# Loginator.net
KiCad netlist of a schematic drawn in EAGLE
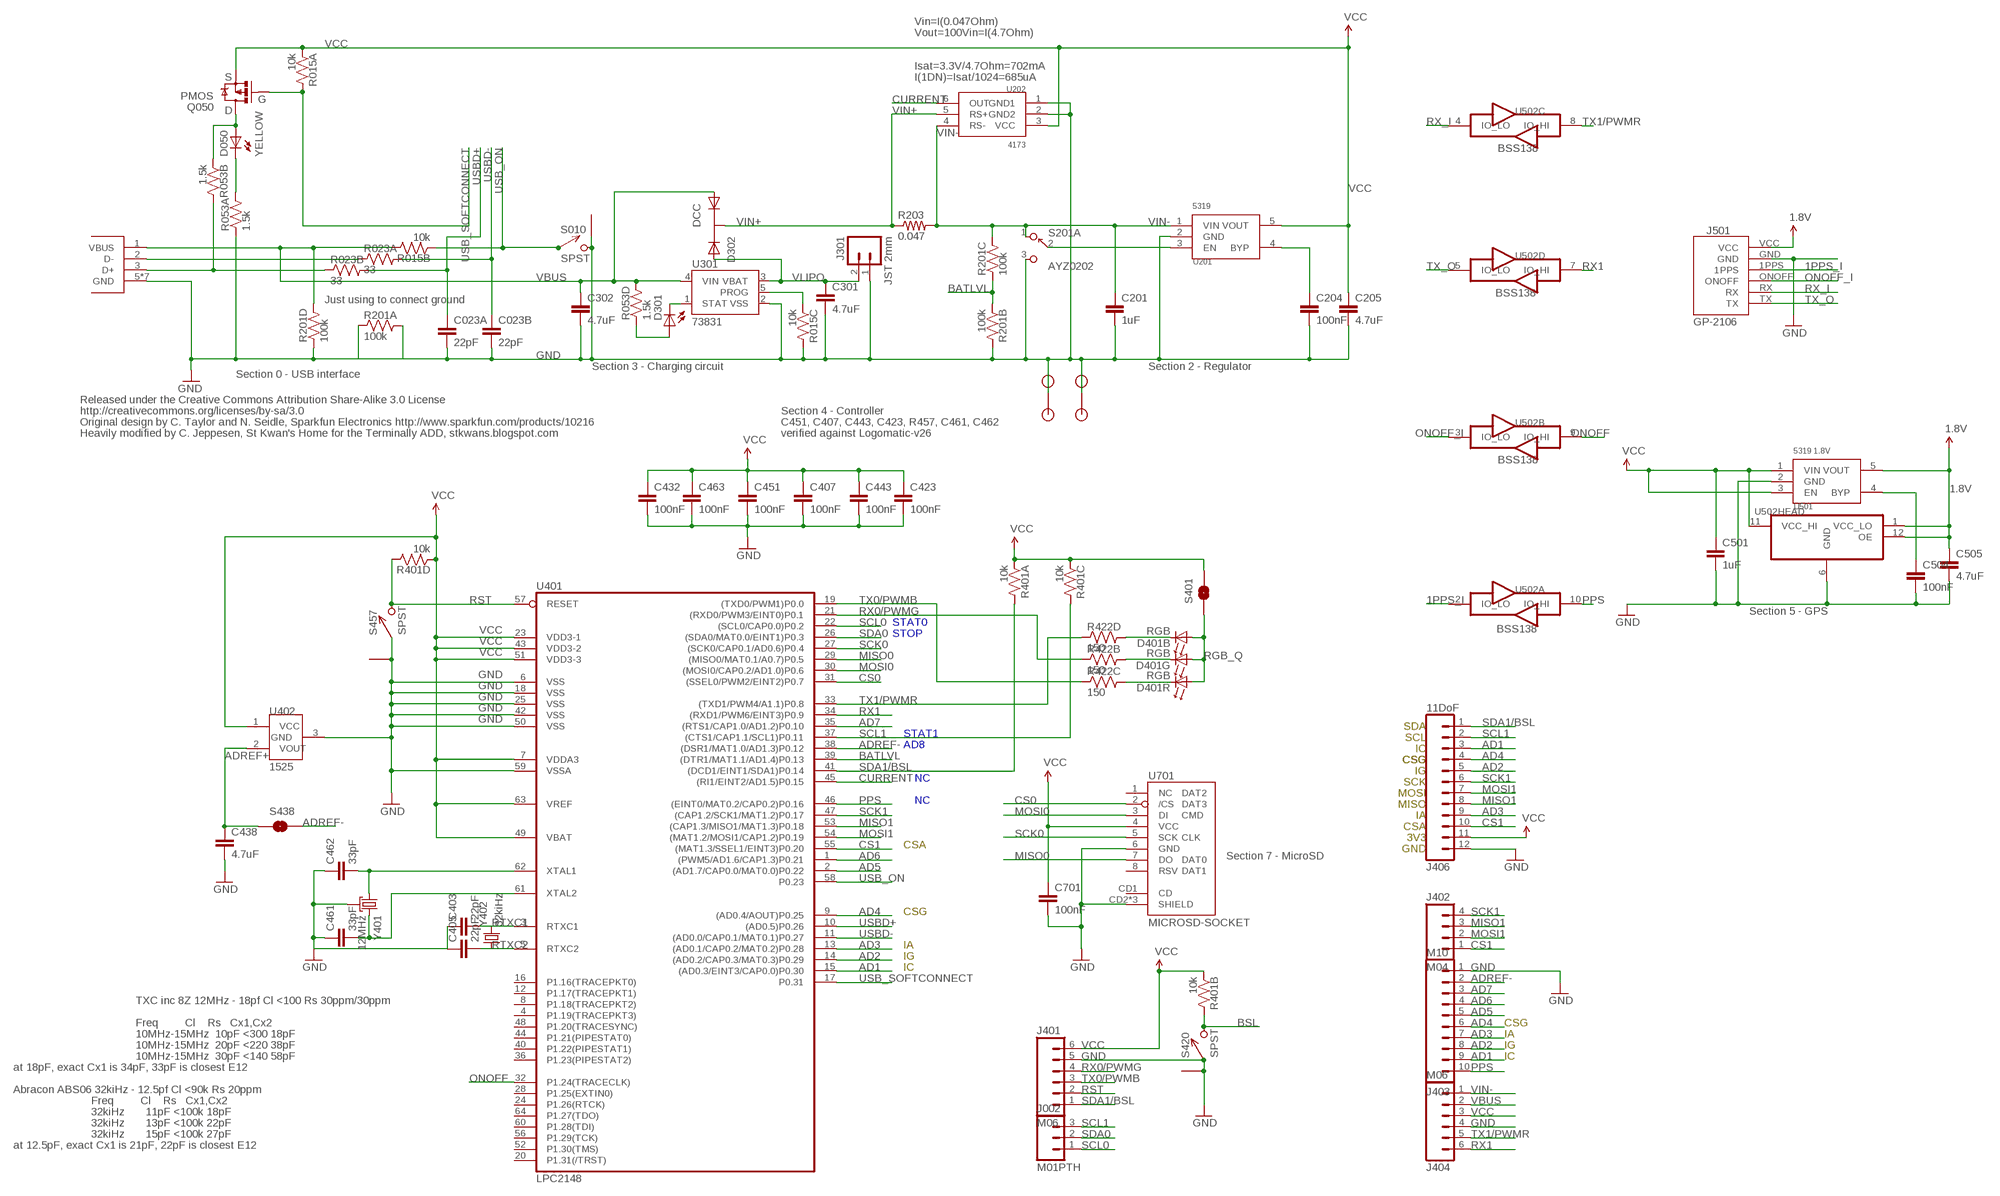
[diagram p0: schematic, sheet 1]

(export (version "E")
  (design (tool "Eeschema 10.0.6"))
  (components
    (comp (ref "C023")
      (value "22pF")
      (footprint "eagle-import:CKCM25")
      (fields (field (name "DIGIKEY") "445-1860-1-ND"))
      (libsource (lib "eagle-import") (part "CKCM25"))
    )
    (comp (ref "C201")
      (value "1uF")
      (footprint "eagle-import:0402-CAP")
      (libsource (lib "eagle-import") (part "CAP0402-CAP"))
    )
    (comp (ref "C204")
      (value "100nF")
      (footprint "eagle-import:0402-CAP")
      (libsource (lib "eagle-import") (part "CAP0402-CAP"))
    )
    (comp (ref "C205")
      (value "4.7uF")
      (footprint "eagle-import:0402-CAP")
      (libsource (lib "eagle-import") (part "CAP0402-CAP"))
    )
    (comp (ref "C301")
      (value "4.7uF")
      (footprint "eagle-import:0402-CAP")
      (libsource (lib "eagle-import") (part "CAP0402-CAP"))
    )
    (comp (ref "C302")
      (value "4.7uF")
      (footprint "eagle-import:0402-CAP")
      (libsource (lib "eagle-import") (part "CAP0402-CAP"))
    )
    (comp (ref "C403")
      (value "22pF")
      (footprint "eagle-import:0402-CAP")
      (libsource (lib "eagle-import") (part "CAP0402-CAP"))
    )
    (comp (ref "C405")
      (value "22pF")
      (footprint "eagle-import:0402-CAP")
      (libsource (lib "eagle-import") (part "CAP0402-CAP"))
    )
    (comp (ref "C407")
      (value "100nF")
      (footprint "eagle-import:0402-CAP")
      (libsource (lib "eagle-import") (part "CAP0402-CAP"))
    )
    (comp (ref "C423")
      (value "100nF")
      (footprint "eagle-import:0402-CAP")
      (libsource (lib "eagle-import") (part "CAP0402-CAP"))
    )
    (comp (ref "C432")
      (value "100nF")
      (footprint "eagle-import:0402-CAP")
      (libsource (lib "eagle-import") (part "CAP0402-CAP"))
    )
    (comp (ref "C438")
      (value "4.7uF")
      (footprint "eagle-import:0402-CAP")
      (libsource (lib "eagle-import") (part "CAP0402-CAP"))
    )
    (comp (ref "C443")
      (value "100nF")
      (footprint "eagle-import:0402-CAP")
      (libsource (lib "eagle-import") (part "CAP0402-CAP"))
    )
    (comp (ref "C451")
      (value "100nF")
      (footprint "eagle-import:0402-CAP")
      (libsource (lib "eagle-import") (part "CAP0402-CAP"))
    )
    (comp (ref "C461")
      (value "33pF")
      (footprint "eagle-import:0402-CAP")
      (libsource (lib "eagle-import") (part "CAP0402-CAP"))
    )
    (comp (ref "C462")
      (value "33pF")
      (footprint "eagle-import:0402-CAP")
      (libsource (lib "eagle-import") (part "CAP0402-CAP"))
    )
    (comp (ref "C463")
      (value "100nF")
      (footprint "eagle-import:0402-CAP")
      (libsource (lib "eagle-import") (part "CAP0402-CAP"))
    )
    (comp (ref "C501")
      (value "1uF")
      (footprint "eagle-import:0402-CAP")
      (libsource (lib "eagle-import") (part "CAP0402-CAP"))
    )
    (comp (ref "C504")
      (value "100nF")
      (footprint "eagle-import:0402-CAP")
      (libsource (lib "eagle-import") (part "CAP0402-CAP"))
    )
    (comp (ref "C505")
      (value "4.7uF")
      (footprint "eagle-import:0402-CAP")
      (libsource (lib "eagle-import") (part "CAP0402-CAP"))
    )
    (comp (ref "C701")
      (value "100nF")
      (footprint "eagle-import:0402-CAP")
      (libsource (lib "eagle-import") (part "CAP0402-CAP"))
    )
    (comp (ref "D050")
      (value "YELLOW")
      (footprint "eagle-import:LED-0603")
      (libsource (lib "eagle-import") (part "LED0603"))
    )
    (comp (ref "D301")
      (value "BLUE")
      (footprint "eagle-import:LED-0603")
      (libsource (lib "eagle-import") (part "LED0603"))
    )
    (comp (ref "D302")
      (value "DCC")
      (footprint "eagle-import:SOT-23-3")
      (libsource (lib "eagle-import") (part "PMEG2005CT"))
    )
    (comp (ref "D401")
      (value "RGB")
      (footprint "eagle-import:SMLP36")
      (fields (field (name "DIGIKEY") "846-1097-1-ND"))
      (libsource (lib "eagle-import") (part "SMLP36RGB2W(R)"))
    )
    (comp (ref "J001")
      (value "USB_MICROB_JSTGCT")
      (footprint "eagle-import:USB_MICROB_3075")
      (libsource (lib "eagle-import") (part "USB_MICROB_JSTGCT"))
    )
    (comp (ref "J002")
      (value "M01PTH")
      (footprint "eagle-import:1X03")
      (libsource (lib "eagle-import") (part "M03PTH"))
    )
    (comp (ref "J301")
      (value "JST 2mm")
      (footprint "eagle-import:JST-2-SMD")
      (libsource (lib "eagle-import") (part "M02-JST-2MM-SMT"))
    )
    (comp (ref "J401")
      (value "M06")
      (footprint "eagle-import:1X06")
      (libsource (lib "eagle-import") (part "M06SIP"))
    )
    (comp (ref "J402")
      (value "M04")
      (footprint "eagle-import:1X04")
      (libsource (lib "eagle-import") (part "M04PTH"))
    )
    (comp (ref "J403")
      (value "M10")
      (footprint "eagle-import:1X10")
      (libsource (lib "eagle-import") (part "M10{dblquote}"))
    )
    (comp (ref "J404")
      (value "M06")
      (footprint "eagle-import:1X06")
      (libsource (lib "eagle-import") (part "M06SIP"))
    )
    (comp (ref "J406")
      (value "11DoF")
      (footprint "eagle-import:1X12")
      (libsource (lib "eagle-import") (part "M12PTH"))
    )
    (comp (ref "J501")
      (value "GP-2106")
      (footprint "eagle-import:GP-2106")
      (libsource (lib "eagle-import") (part "GP-2106"))
    )
    (comp (ref "JP1")
      (value "STANDOFF")
      (footprint "eagle-import:STANDOFF")
      (libsource (lib "eagle-import") (part "STANDOFF"))
    )
    (comp (ref "JP2")
      (value "STANDOFF")
      (footprint "eagle-import:STANDOFF")
      (libsource (lib "eagle-import") (part "STANDOFF"))
    )
    (comp (ref "JP3")
      (value "STANDOFF")
      (footprint "eagle-import:STANDOFF")
      (libsource (lib "eagle-import") (part "STANDOFF"))
    )
    (comp (ref "JP4")
      (value "STANDOFF")
      (footprint "eagle-import:STANDOFF")
      (libsource (lib "eagle-import") (part "STANDOFF"))
    )
    (comp (ref "Q050")
      (value "PMOS")
      (footprint "eagle-import:SOT23-3")
      (libsource (lib "eagle-import") (part "MOSFET-PCHANNELSMD"))
    )
    (comp (ref "R015")
      (value "10k")
      (footprint "eagle-import:CRA04")
      (fields (field (name "DIGIKEY") "CRA4S810KCT-ND"))
      (libsource (lib "eagle-import") (part "RP404"))
    )
    (comp (ref "R023")
      (value "33")
      (footprint "eagle-import:CRA02")
      (fields (field (name "DIGIKEY") "Y5330CT-ND"))
      (libsource (lib "eagle-import") (part "RP2EXB24V"))
    )
    (comp (ref "R053")
      (value "1.5k")
      (footprint "eagle-import:CRA04")
      (fields (field (name "DIGIKEY") "CRA4S81.5KCT-ND"))
      (libsource (lib "eagle-import") (part "RP404"))
    )
    (comp (ref "R201")
      (value "100k")
      (footprint "eagle-import:CRA04")
      (fields (field (name "DIGIKEY") "CRA4S8100KCT-ND"))
      (libsource (lib "eagle-import") (part "RP404"))
    )
    (comp (ref "R203")
      (value "0.047")
      (footprint "eagle-import:0402-RES")
      (libsource (lib "eagle-import") (part "RESISTOR0402-RES"))
    )
    (comp (ref "R401")
      (value "10k")
      (footprint "eagle-import:CRA04")
      (fields (field (name "DIGIKEY") "CRA4S810KCT-ND"))
      (libsource (lib "eagle-import") (part "RP404"))
    )
    (comp (ref "R422")
      (value "150")
      (footprint "eagle-import:CRA04")
      (fields (field (name "DIGIKEY") "CRA4P8150CT-ND"))
      (libsource (lib "eagle-import") (part "RP404"))
    )
    (comp (ref "S010")
      (value "SPST")
      (footprint "eagle-import:B3U-1100P")
      (fields (field (name "DIGIKEY") "SW1021CT-ND"))
      (libsource (lib "eagle-import") (part "B3U-1100P"))
    )
    (comp (ref "S201")
      (value "AYZ0202")
      (footprint "eagle-import:AYZ0202")
      (libsource (lib "eagle-import") (part "AYZ0202"))
    )
    (comp (ref "S401")
      (value "SOLDERJUMPERNO")
      (footprint "eagle-import:SJ_2S-NO")
      (libsource (lib "eagle-import") (part "SOLDERJUMPERNO"))
    )
    (comp (ref "S420")
      (value "SPST")
      (footprint "eagle-import:B3U-1100P")
      (fields (field (name "DIGIKEY") "SW1021CT-ND"))
      (libsource (lib "eagle-import") (part "B3U-1100P"))
    )
    (comp (ref "S438")
      (value "SOLDERJUMPERNO")
      (footprint "eagle-import:SJ_2S-NO")
      (libsource (lib "eagle-import") (part "SOLDERJUMPERNO"))
    )
    (comp (ref "S457")
      (value "SPST")
      (footprint "eagle-import:B3U-1100P")
      (fields (field (name "DIGIKEY") "SW1021CT-ND"))
      (libsource (lib "eagle-import") (part "B3U-1100P"))
    )
    (comp (ref "U201")
      (value "5319")
      (footprint "eagle-import:SOT-23-5")
      (libsource (lib "eagle-import") (part "MIC5319D5"))
    )
    (comp (ref "U202")
      (value "4173")
      (footprint "eagle-import:SOT-23-6")
      (libsource (lib "eagle-import") (part "MAX4173"))
    )
    (comp (ref "U301")
      (value "73831")
      (footprint "eagle-import:SOT23-5")
      (libsource (lib "eagle-import") (part "MCP73831"))
    )
    (comp (ref "U401")
      (value "LPC2148")
      (footprint "eagle-import:SQFP-S-10X10-64")
      (libsource (lib "eagle-import") (part "LPC213X"))
    )
    (comp (ref "U402")
      (value "1525")
      (footprint "eagle-import:SOT-23-3")
      (libsource (lib "eagle-import") (part "MCP1525"))
    )
    (comp (ref "U501")
      (value "5319 1.8V")
      (footprint "eagle-import:SOT-23-5")
      (libsource (lib "eagle-import") (part "MIC5319D5"))
    )
    (comp (ref "U502")
      (value "TXB0104RUT")
      (footprint "eagle-import:R-PUQFN-N12")
      (fields (field (name "DIGIKEY") "296-25888-1-ND"))
      (libsource (lib "eagle-import") (part "TXB0104RUT"))
    )
    (comp (ref "U701")
      (value "MICROSD-SOCKET")
      (footprint "eagle-import:MICROSD-SOCKET-PP")
      (libsource (lib "eagle-import") (part "MICROSD-SOCKET"))
    )
    (comp (ref "Y401")
      (value "12MHz")
      (footprint "eagle-import:CRYSTAL_SMD_2MM_2_5MM")
      (libsource (lib "eagle-import") (part "CX2520"))
    )
    (comp (ref "Y402")
      (value "32kiHz")
      (footprint "eagle-import:ABS06")
      (libsource (lib "eagle-import") (part "ABS06"))
    )
  )
  (nets
    (net (code "1") (name "/1PPS_I") (class "Default")
      (node (ref "J501") (pin "1PPS") (pinfunction "1PPS_1PPS") (pintype "bidirectional"))
      (node (ref "U502") (pin "2") (pinfunction "IO_LO_2") (pintype "bidirectional"))
    )
    (net (code "2") (name "/AD1") (class "Default")
      (node (ref "J403") (pin "9") (pinfunction "9_9") (pintype "passive"))
      (node (ref "J406") (pin "3") (pinfunction "3_3") (pintype "passive"))
      (node (ref "U401") (pin "15") (pinfunction "(AD0.3/EINT3/CAP0.0)P0.30_15") (pintype "bidirectional"))
    )
    (net (code "3") (name "/AD2") (class "Default")
      (node (ref "J403") (pin "8") (pinfunction "8_8") (pintype "passive"))
      (node (ref "J406") (pin "5") (pinfunction "5_5") (pintype "passive"))
      (node (ref "U401") (pin "14") (pinfunction "(AD0.2/CAP0.3/MAT0.3)P0.29_14") (pintype "bidirectional"))
    )
    (net (code "4") (name "/AD3") (class "Default")
      (node (ref "J403") (pin "7") (pinfunction "7_7") (pintype "passive"))
      (node (ref "J406") (pin "9") (pinfunction "9_9") (pintype "passive"))
      (node (ref "U401") (pin "13") (pinfunction "(AD0.1/CAP0.2/MAT0.2)P0.28_13") (pintype "bidirectional"))
    )
    (net (code "5") (name "/AD4") (class "Default")
      (node (ref "J403") (pin "6") (pinfunction "6_6") (pintype "passive"))
      (node (ref "J406") (pin "4") (pinfunction "4_4") (pintype "passive"))
      (node (ref "U401") (pin "9") (pinfunction "(AD0.4/AOUT)P0.25_9") (pintype "bidirectional"))
    )
    (net (code "6") (name "/AD5") (class "Default")
      (node (ref "J403") (pin "5") (pinfunction "5_5") (pintype "passive"))
      (node (ref "U401") (pin "2") (pinfunction "(AD1.7/CAP0.0/MAT0.0)P0.22_2") (pintype "bidirectional"))
    )
    (net (code "7") (name "/AD6") (class "Default")
      (node (ref "J403") (pin "4") (pinfunction "4_4") (pintype "passive"))
      (node (ref "U401") (pin "1") (pinfunction "(PWM5/AD1.6/CAP1.3)P0.21_1") (pintype "bidirectional"))
    )
    (net (code "8") (name "/AD7") (class "Default")
      (node (ref "J403") (pin "3") (pinfunction "3_3") (pintype "passive"))
      (node (ref "U401") (pin "35") (pinfunction "(RTS1/CAP1.0/AD1.2)P0.10_35") (pintype "bidirectional"))
    )
    (net (code "9") (name "/ADREF+") (class "Default")
      (node (ref "C438") (pin "1") (pinfunction "1_1") (pintype "passive"))
      (node (ref "S438") (pin "1") (pinfunction "1_1") (pintype "passive"))
      (node (ref "U402") (pin "2") (pinfunction "VOUT_2") (pintype "bidirectional"))
    )
    (net (code "10") (name "/ADREF-") (class "Default")
      (node (ref "J403") (pin "2") (pinfunction "2_2") (pintype "passive"))
      (node (ref "S438") (pin "2") (pinfunction "2_2") (pintype "passive"))
      (node (ref "U401") (pin "38") (pinfunction "(DSR1/MAT1.0/AD1.3)P0.12_38") (pintype "bidirectional"))
    )
    (net (code "11") (name "/BATLVL") (class "Default")
      (node (ref "R201") (pin "2") (pinfunction "1_2") (pintype "passive"))
      (node (ref "R201") (pin "3") (pinfunction "1_3") (pintype "passive"))
      (node (ref "U401") (pin "39") (pinfunction "(DTR1/MAT1.1/AD1.4)P0.13_39") (pintype "bidirectional"))
    )
    (net (code "12") (name "/BSL") (class "Default")
      (node (ref "R401") (pin "7") (pinfunction "2_7") (pintype "passive"))
      (node (ref "S420") (pin "P$2") (pinfunction "2_P$2") (pintype "bidirectional"))
    )
    (net (code "13") (name "/CS0") (class "Default")
      (node (ref "U401") (pin "31") (pinfunction "(SSEL0/PWM2/EINT2)P0.7_31") (pintype "bidirectional"))
      (node (ref "U701") (pin "2") (pinfunction "/CS_2") (pintype "bidirectional"))
    )
    (net (code "14") (name "/CS1") (class "Default")
      (node (ref "J402") (pin "1") (pinfunction "1_1") (pintype "passive"))
      (node (ref "J406") (pin "10") (pinfunction "10_10") (pintype "passive"))
      (node (ref "U401") (pin "55") (pinfunction "(MAT1.3/SSEL1/EINT3)P0.20_55") (pintype "bidirectional"))
    )
    (net (code "15") (name "/CURRENT") (class "Default")
      (node (ref "U202") (pin "6") (pinfunction "OUT_6") (pintype "bidirectional"))
      (node (ref "U401") (pin "45") (pinfunction "(RI1/EINT2/AD1.5)P0.15_45") (pintype "bidirectional"))
    )
    (net (code "16") (name "/MISO0") (class "Default")
      (node (ref "U401") (pin "29") (pinfunction "(MISO0/MAT0.1/A0.7)P0.5_29") (pintype "bidirectional"))
      (node (ref "U701") (pin "7") (pinfunction "DO_7") (pintype "bidirectional"))
    )
    (net (code "17") (name "/MISO1") (class "Default")
      (node (ref "J402") (pin "3") (pinfunction "3_3") (pintype "passive"))
      (node (ref "J406") (pin "8") (pinfunction "8_8") (pintype "passive"))
      (node (ref "U401") (pin "53") (pinfunction "(CAP1.3/MISO1/MAT1.3)P0.18_53") (pintype "bidirectional"))
    )
    (net (code "18") (name "/MOSI0") (class "Default")
      (node (ref "U401") (pin "30") (pinfunction "(MOSI0/CAP0.2/AD1.0)P0.6_30") (pintype "bidirectional"))
      (node (ref "U701") (pin "3") (pinfunction "DI_3") (pintype "bidirectional"))
    )
    (net (code "19") (name "/MOSI1") (class "Default")
      (node (ref "J402") (pin "2") (pinfunction "2_2") (pintype "passive"))
      (node (ref "J406") (pin "7") (pinfunction "7_7") (pintype "passive"))
      (node (ref "U401") (pin "54") (pinfunction "(MAT1.2/MOSI1/CAP1.2)P0.19_54") (pintype "bidirectional"))
    )
    (net (code "20") (name "/ONOFF") (class "Default")
      (node (ref "U401") (pin "32") (pinfunction "P1.24(TRACECLK)_32") (pintype "bidirectional"))
      (node (ref "U502") (pin "9") (pinfunction "IO_HI_9") (pintype "bidirectional"))
    )
    (net (code "21") (name "/ONOFF_I") (class "Default")
      (node (ref "J501") (pin "ONOFF") (pinfunction "ONOFF_ONOFF") (pintype "bidirectional"))
      (node (ref "U502") (pin "3") (pinfunction "IO_LO_3") (pintype "bidirectional"))
    )
    (net (code "22") (name "/PPS") (class "Default")
      (node (ref "J403") (pin "10") (pinfunction "10_10") (pintype "passive"))
      (node (ref "U401") (pin "46") (pinfunction "(EINT0/MAT0.2/CAP0.2)P0.16_46") (pintype "bidirectional"))
      (node (ref "U502") (pin "10") (pinfunction "IO_HI_10") (pintype "bidirectional"))
    )
    (net (code "23") (name "/RGB_Q") (class "Default")
      (node (ref "D401") (pin "2") (pinfunction "A_2") (pintype "passive"))
      (node (ref "D401") (pin "4") (pinfunction "A_4") (pintype "passive"))
      (node (ref "D401") (pin "6") (pinfunction "A_6") (pintype "passive"))
      (node (ref "S401") (pin "1") (pinfunction "1_1") (pintype "passive"))
    )
    (net (code "24") (name "/RST") (class "Default")
      (node (ref "J401") (pin "2") (pinfunction "2_2") (pintype "passive"))
      (node (ref "R401") (pin "5") (pinfunction "2_5") (pintype "passive"))
      (node (ref "S457") (pin "P$2") (pinfunction "2_P$2") (pintype "bidirectional"))
      (node (ref "U401") (pin "57") (pinfunction "RESET_57") (pintype "input"))
    )
    (net (code "25") (name "/RTXC1") (class "Default")
      (node (ref "C403") (pin "2") (pinfunction "2_2") (pintype "passive"))
      (node (ref "U401") (pin "3") (pinfunction "RTXC1_3") (pintype "input"))
      (node (ref "Y402") (pin "2") (pinfunction "2_2") (pintype "passive"))
    )
    (net (code "26") (name "/RTXC2") (class "Default")
      (node (ref "C405") (pin "2") (pinfunction "2_2") (pintype "passive"))
      (node (ref "U401") (pin "5") (pinfunction "RTXC2_5") (pintype "output"))
      (node (ref "Y402") (pin "1") (pinfunction "1_1") (pintype "passive"))
    )
    (net (code "27") (name "/RX0{slash}PWMG") (class "Default")
      (node (ref "J401") (pin "4") (pinfunction "4_4") (pintype "passive"))
      (node (ref "R422") (pin "2") (pinfunction "1_2") (pintype "passive"))
      (node (ref "U401") (pin "21") (pinfunction "(RXD0/PWM3/EINT0)P0.1_21") (pintype "bidirectional"))
    )
    (net (code "28") (name "/RX1") (class "Default")
      (node (ref "J404") (pin "6") (pinfunction "6_6") (pintype "passive"))
      (node (ref "U401") (pin "34") (pinfunction "(RXD1/PWM6/EINT3)P0.9_34") (pintype "bidirectional"))
      (node (ref "U502") (pin "7") (pinfunction "IO_HI_7") (pintype "bidirectional"))
    )
    (net (code "29") (name "/RX_I") (class "Default")
      (node (ref "J501") (pin "RX") (pinfunction "RX_RX") (pintype "bidirectional"))
      (node (ref "U502") (pin "4") (pinfunction "IO_LO_4") (pintype "bidirectional"))
    )
    (net (code "30") (name "/SCK0") (class "Default")
      (node (ref "U401") (pin "27") (pinfunction "(SCK0/CAP0.1/AD0.6)P0.4_27") (pintype "bidirectional"))
      (node (ref "U701") (pin "5") (pinfunction "SCK_5") (pintype "bidirectional"))
    )
    (net (code "31") (name "/SCK1") (class "Default")
      (node (ref "J402") (pin "4") (pinfunction "4_4") (pintype "passive"))
      (node (ref "J406") (pin "6") (pinfunction "6_6") (pintype "passive"))
      (node (ref "U401") (pin "47") (pinfunction "(CAP1.2/SCK1/MAT1.2)P0.17_47") (pintype "bidirectional"))
    )
    (net (code "32") (name "/SCL0") (class "Default")
      (node (ref "J002") (pin "1") (pinfunction "1_1") (pintype "passive"))
      (node (ref "U401") (pin "22") (pinfunction "(SCL0/CAP0.0)P0.2_22") (pintype "bidirectional"))
    )
    (net (code "33") (name "/SCL1") (class "Default")
      (node (ref "J002") (pin "3") (pinfunction "3_3") (pintype "passive"))
      (node (ref "J406") (pin "2") (pinfunction "2_2") (pintype "passive"))
      (node (ref "R401") (pin "6") (pinfunction "2_6") (pintype "passive"))
      (node (ref "U401") (pin "37") (pinfunction "(CTS1/CAP1.1/SCL1)P0.11_37") (pintype "bidirectional"))
    )
    (net (code "34") (name "/SDA0") (class "Default")
      (node (ref "J002") (pin "2") (pinfunction "2_2") (pintype "passive"))
      (node (ref "U401") (pin "26") (pinfunction "(SDA0/MAT0.0/EINT1)P0.3_26") (pintype "bidirectional"))
    )
    (net (code "35") (name "/SDA1{slash}BSL") (class "Default")
      (node (ref "J401") (pin "1") (pinfunction "1_1") (pintype "passive"))
      (node (ref "J406") (pin "1") (pinfunction "1_1") (pintype "passive"))
      (node (ref "R401") (pin "8") (pinfunction "2_8") (pintype "passive"))
      (node (ref "U401") (pin "41") (pinfunction "(DCD1/EINT1/SDA1)P0.14_41") (pintype "bidirectional"))
    )
    (net (code "36") (name "/TX0{slash}PWMB") (class "Default")
      (node (ref "J401") (pin "3") (pinfunction "3_3") (pintype "passive"))
      (node (ref "R422") (pin "3") (pinfunction "1_3") (pintype "passive"))
      (node (ref "U401") (pin "19") (pinfunction "(TXD0/PWM1)P0.0_19") (pintype "bidirectional"))
    )
    (net (code "37") (name "/TX1{slash}PWMR") (class "Default")
      (node (ref "J404") (pin "5") (pinfunction "5_5") (pintype "passive"))
      (node (ref "R422") (pin "4") (pinfunction "1_4") (pintype "passive"))
      (node (ref "U401") (pin "33") (pinfunction "(TXD1/PWM4/A1.1)P0.8_33") (pintype "bidirectional"))
      (node (ref "U502") (pin "8") (pinfunction "IO_HI_8") (pintype "bidirectional"))
    )
    (net (code "38") (name "/TX_O") (class "Default")
      (node (ref "J501") (pin "TX") (pinfunction "TX_TX") (pintype "bidirectional"))
      (node (ref "U502") (pin "5") (pinfunction "IO_LO_5") (pintype "bidirectional"))
    )
    (net (code "39") (name "/USBD+") (class "Default")
      (node (ref "C023") (pin "1") (pinfunction "1_1") (pintype "passive"))
      (node (ref "R023") (pin "3") (pinfunction "2_3") (pintype "passive"))
      (node (ref "U401") (pin "10") (pinfunction "(AD0.5)P0.26_10") (pintype "bidirectional"))
    )
    (net (code "40") (name "/USBD-") (class "Default")
      (node (ref "C023") (pin "2") (pinfunction "1_2") (pintype "passive"))
      (node (ref "R023") (pin "4") (pinfunction "2_4") (pintype "passive"))
      (node (ref "U401") (pin "11") (pinfunction "(AD0.0/CAP0.1/MAT0.1)P0.27_11") (pintype "bidirectional"))
    )
    (net (code "41") (name "/USB_ON") (class "Default")
      (node (ref "R015") (pin "2") (pinfunction "1_2") (pintype "passive"))
      (node (ref "S010") (pin "P$1") (pinfunction "1_P$1") (pintype "bidirectional"))
      (node (ref "U401") (pin "58") (pinfunction "P0.23_58") (pintype "bidirectional"))
    )
    (net (code "42") (name "/USB_SOFTCONNECT") (class "Default")
      (node (ref "Q050") (pin "1") (pinfunction "G_1") (pintype "passive"))
      (node (ref "R015") (pin "8") (pinfunction "2_8") (pintype "passive"))
      (node (ref "U401") (pin "17") (pinfunction "P0.31_17") (pintype "output"))
    )
    (net (code "43") (name "/VBUS") (class "Default")
      (node (ref "C302") (pin "1") (pinfunction "1_1") (pintype "passive"))
      (node (ref "D302") (pin "1") (pinfunction "A1_1") (pintype "passive"))
      (node (ref "J001") (pin "1") (pinfunction "VBUS_1") (pintype "bidirectional"))
      (node (ref "J404") (pin "2") (pinfunction "2_2") (pintype "passive"))
      (node (ref "R015") (pin "7") (pinfunction "2_7") (pintype "passive"))
      (node (ref "R053") (pin "5") (pinfunction "2_5") (pintype "passive"))
      (node (ref "R201") (pin "5") (pinfunction "2_5") (pintype "passive"))
      (node (ref "U301") (pin "4") (pinfunction "VIN_4") (pintype "power_in"))
    )
    (net (code "44") (name "/VIN+") (class "Default")
      (node (ref "D302") (pin "3") (pinfunction "K_3") (pintype "passive"))
      (node (ref "R203") (pin "1") (pinfunction "1_1") (pintype "passive"))
      (node (ref "U202") (pin "5") (pinfunction "RS+_5") (pintype "bidirectional"))
    )
    (net (code "45") (name "/VIN-") (class "Default")
      (node (ref "C201") (pin "1") (pinfunction "1_1") (pintype "passive"))
      (node (ref "J404") (pin "1") (pinfunction "1_1") (pintype "passive"))
      (node (ref "R201") (pin "6") (pinfunction "2_6") (pintype "passive"))
      (node (ref "R203") (pin "2") (pinfunction "2_2") (pintype "passive"))
      (node (ref "S201") (pin "1") (pinfunction "P$1_1") (pintype "bidirectional"))
      (node (ref "U201") (pin "1") (pinfunction "VIN_1") (pintype "bidirectional"))
      (node (ref "U202") (pin "4") (pinfunction "RS-_4") (pintype "bidirectional"))
    )
    (net (code "46") (name "/VLIPO") (class "Default")
      (node (ref "C301") (pin "1") (pinfunction "1_1") (pintype "passive"))
      (node (ref "D302") (pin "2") (pinfunction "A2_2") (pintype "passive"))
      (node (ref "J301") (pin "2") (pinfunction "2_2") (pintype "passive"))
      (node (ref "U301") (pin "3") (pinfunction "VBAT_3") (pintype "power_in"))
    )
    (net (code "47") (name "1.8V") (class "Default")
      (node (ref "C505") (pin "1") (pinfunction "1_1") (pintype "passive"))
      (node (ref "J501") (pin "VCC") (pinfunction "VCC_VCC") (pintype "bidirectional"))
      (node (ref "U501") (pin "5") (pinfunction "VOUT_5") (pintype "bidirectional"))
      (node (ref "U502") (pin "1") (pinfunction "VCC_LO_1") (pintype "power_in"))
      (node (ref "U502") (pin "12") (pinfunction "OE_12") (pintype "bidirectional"))
    )
    (net (code "48") (name "GND") (class "Default")
      (node (ref "C023") (pin "3") (pinfunction "2_3") (pintype "passive"))
      (node (ref "C023") (pin "4") (pinfunction "2_4") (pintype "passive"))
      (node (ref "C201") (pin "2") (pinfunction "2_2") (pintype "passive"))
      (node (ref "C204") (pin "2") (pinfunction "2_2") (pintype "passive"))
      (node (ref "C205") (pin "2") (pinfunction "2_2") (pintype "passive"))
      (node (ref "C301") (pin "2") (pinfunction "2_2") (pintype "passive"))
      (node (ref "C302") (pin "2") (pinfunction "2_2") (pintype "passive"))
      (node (ref "C403") (pin "1") (pinfunction "1_1") (pintype "passive"))
      (node (ref "C405") (pin "1") (pinfunction "1_1") (pintype "passive"))
      (node (ref "C407") (pin "2") (pinfunction "2_2") (pintype "passive"))
      (node (ref "C423") (pin "2") (pinfunction "2_2") (pintype "passive"))
      (node (ref "C432") (pin "2") (pinfunction "2_2") (pintype "passive"))
      (node (ref "C438") (pin "2") (pinfunction "2_2") (pintype "passive"))
      (node (ref "C443") (pin "2") (pinfunction "2_2") (pintype "passive"))
      (node (ref "C451") (pin "2") (pinfunction "2_2") (pintype "passive"))
      (node (ref "C461") (pin "1") (pinfunction "1_1") (pintype "passive"))
      (node (ref "C462") (pin "1") (pinfunction "1_1") (pintype "passive"))
      (node (ref "C463") (pin "2") (pinfunction "2_2") (pintype "passive"))
      (node (ref "C501") (pin "2") (pinfunction "2_2") (pintype "passive"))
      (node (ref "C504") (pin "2") (pinfunction "2_2") (pintype "passive"))
      (node (ref "C505") (pin "2") (pinfunction "2_2") (pintype "passive"))
      (node (ref "C701") (pin "2") (pinfunction "2_2") (pintype "passive"))
      (node (ref "J001") (pin "5") (pinfunction "GND_5") (pintype "bidirectional"))
      (node (ref "J001") (pin "P$1") (pinfunction "GND_P$1") (pintype "bidirectional"))
      (node (ref "J001") (pin "P$10") (pinfunction "GND_P$10") (pintype "bidirectional"))
      (node (ref "J001") (pin "P$2") (pinfunction "GND_P$2") (pintype "bidirectional"))
      (node (ref "J001") (pin "P$3") (pinfunction "GND_P$3") (pintype "bidirectional"))
      (node (ref "J001") (pin "P$4") (pinfunction "GND_P$4") (pintype "bidirectional"))
      (node (ref "J001") (pin "P$8") (pinfunction "GND_P$8") (pintype "bidirectional"))
      (node (ref "J301") (pin "1") (pinfunction "1_1") (pintype "passive"))
      (node (ref "J401") (pin "5") (pinfunction "5_5") (pintype "passive"))
      (node (ref "J403") (pin "1") (pinfunction "1_1") (pintype "passive"))
      (node (ref "J404") (pin "4") (pinfunction "4_4") (pintype "passive"))
      (node (ref "J406") (pin "12") (pinfunction "12_12") (pintype "passive"))
      (node (ref "J501") (pin "GND") (pinfunction "GND_GND") (pintype "bidirectional"))
      (node (ref "JP1") (pin "P$1") (pinfunction "P$1_P$1") (pintype "bidirectional"))
      (node (ref "JP2") (pin "P$1") (pinfunction "P$1_P$1") (pintype "bidirectional"))
      (node (ref "JP3") (pin "P$1") (pinfunction "P$1_P$1") (pintype "bidirectional"))
      (node (ref "JP4") (pin "P$1") (pinfunction "P$1_P$1") (pintype "bidirectional"))
      (node (ref "R015") (pin "6") (pinfunction "2_6") (pintype "passive"))
      (node (ref "R053") (pin "1") (pinfunction "1_1") (pintype "passive"))
      (node (ref "R201") (pin "1") (pinfunction "1_1") (pintype "passive"))
      (node (ref "R201") (pin "4") (pinfunction "1_4") (pintype "passive"))
      (node (ref "R201") (pin "7") (pinfunction "2_7") (pintype "passive"))
      (node (ref "R201") (pin "8") (pinfunction "2_8") (pintype "passive"))
      (node (ref "S010") (pin "P$2") (pinfunction "2_P$2") (pintype "bidirectional"))
      (node (ref "S010") (pin "P$3") (pinfunction "1_P$3") (pintype "bidirectional"))
      (node (ref "S201") (pin "3") (pinfunction "P$2_3") (pintype "bidirectional"))
      (node (ref "S420") (pin "P$1") (pinfunction "1_P$1") (pintype "bidirectional"))
      (node (ref "S420") (pin "P$3") (pinfunction "1_P$3") (pintype "bidirectional"))
      (node (ref "S457") (pin "P$1") (pinfunction "1_P$1") (pintype "bidirectional"))
      (node (ref "S457") (pin "P$3") (pinfunction "1_P$3") (pintype "bidirectional"))
      (node (ref "U201") (pin "2") (pinfunction "GND_2") (pintype "bidirectional"))
      (node (ref "U202") (pin "1") (pinfunction "GND1_1") (pintype "bidirectional"))
      (node (ref "U202") (pin "2") (pinfunction "GND2_2") (pintype "bidirectional"))
      (node (ref "U301") (pin "2") (pinfunction "VSS_2") (pintype "power_in"))
      (node (ref "U401") (pin "18") (pinfunction "VSS_18") (pintype "power_in"))
      (node (ref "U401") (pin "25") (pinfunction "VSS_25") (pintype "power_in"))
      (node (ref "U401") (pin "42") (pinfunction "VSS_42") (pintype "power_in"))
      (node (ref "U401") (pin "50") (pinfunction "VSS_50") (pintype "power_in"))
      (node (ref "U401") (pin "59") (pinfunction "VSSA_59") (pintype "power_in"))
      (node (ref "U401") (pin "6") (pinfunction "VSS_6") (pintype "power_in"))
      (node (ref "U402") (pin "3") (pinfunction "GND_3") (pintype "bidirectional"))
      (node (ref "U501") (pin "2") (pinfunction "GND_2") (pintype "bidirectional"))
      (node (ref "U502") (pin "6") (pinfunction "GND_6") (pintype "power_in"))
      (node (ref "U701") (pin "6") (pinfunction "GND_6") (pintype "bidirectional"))
      (node (ref "U701") (pin "CD2") (pinfunction "SHIELD_CD2") (pintype "bidirectional"))
      (node (ref "U701") (pin "GND1") (pinfunction "SHIELD_GND1") (pintype "bidirectional"))
      (node (ref "U701") (pin "GND3") (pinfunction "SHIELD_GND3") (pintype "bidirectional"))
      (node (ref "Y401") (pin "2") (pinfunction "GND_2") (pintype "passive"))
      (node (ref "Y401") (pin "4") (pinfunction "GND_4") (pintype "passive"))
    )
    (net (code "49") (name "Net-(D401A-C)") (class "Default")
      (node (ref "D401") (pin "1") (pinfunction "C_1") (pintype "passive"))
      (node (ref "R422") (pin "5") (pinfunction "2_5") (pintype "passive"))
    )
    (net (code "50") (name "Net-(D401B-C)") (class "Default")
      (node (ref "D401") (pin "5") (pinfunction "C_5") (pintype "passive"))
      (node (ref "R422") (pin "7") (pinfunction "2_7") (pintype "passive"))
    )
    (net (code "51") (name "Net-(D401C-C)") (class "Default")
      (node (ref "D401") (pin "3") (pinfunction "C_3") (pintype "passive"))
      (node (ref "R422") (pin "6") (pinfunction "2_6") (pintype "passive"))
    )
    (net (code "52") (name "Net-(J001-D+)") (class "Default")
      (node (ref "J001") (pin "3") (pinfunction "D+_3") (pintype "bidirectional"))
      (node (ref "R023") (pin "2") (pinfunction "1_2") (pintype "passive"))
      (node (ref "R053") (pin "7") (pinfunction "2_7") (pintype "passive"))
    )
    (net (code "53") (name "Net-(J001-D-)") (class "Default")
      (node (ref "J001") (pin "2") (pinfunction "D-_2") (pintype "bidirectional"))
      (node (ref "R023") (pin "1") (pinfunction "1_1") (pintype "passive"))
    )
    (net (code "54") (name "Net-(Q050-D)") (class "Default")
      (node (ref "D050") (pin "A") (pinfunction "A_A") (pintype "passive"))
      (node (ref "Q050") (pin "3") (pinfunction "D_3") (pintype "passive"))
      (node (ref "R053") (pin "2") (pinfunction "1_2") (pintype "passive"))
    )
    (net (code "55") (name "Net-(R015C-1)") (class "Default")
      (node (ref "R015") (pin "3") (pinfunction "1_3") (pintype "passive"))
      (node (ref "U301") (pin "5") (pinfunction "PROG_5") (pintype "input"))
    )
    (net (code "56") (name "Net-(R053A-2)") (class "Default")
      (node (ref "D050") (pin "C") (pinfunction "C_C") (pintype "passive"))
      (node (ref "R053") (pin "8") (pinfunction "2_8") (pintype "passive"))
    )
    (net (code "57") (name "Net-(R053D-1)") (class "Default")
      (node (ref "D301") (pin "A") (pinfunction "A_A") (pintype "passive"))
      (node (ref "R053") (pin "4") (pinfunction "1_4") (pintype "passive"))
    )
    (net (code "58") (name "Net-(S201A-P$3)") (class "Default")
      (node (ref "S201") (pin "2") (pinfunction "P$3_2") (pintype "bidirectional"))
      (node (ref "U201") (pin "3") (pinfunction "EN_3") (pintype "bidirectional"))
    )
    (net (code "59") (name "Net-(U201-BYP)") (class "Default")
      (node (ref "C204") (pin "1") (pinfunction "1_1") (pintype "passive"))
      (node (ref "U201") (pin "4") (pinfunction "BYP_4") (pintype "bidirectional"))
    )
    (net (code "60") (name "Net-(U301-STAT)") (class "Default")
      (node (ref "D301") (pin "C") (pinfunction "C_C") (pintype "passive"))
      (node (ref "U301") (pin "1") (pinfunction "STAT_1") (pintype "output"))
    )
    (net (code "61") (name "Net-(U401-XTAL1)") (class "Default")
      (node (ref "C462") (pin "2") (pinfunction "2_2") (pintype "passive"))
      (node (ref "U401") (pin "62") (pinfunction "XTAL1_62") (pintype "input"))
      (node (ref "Y401") (pin "1") (pinfunction "1_1") (pintype "passive"))
    )
    (net (code "62") (name "Net-(U401-XTAL2)") (class "Default")
      (node (ref "C461") (pin "2") (pinfunction "2_2") (pintype "passive"))
      (node (ref "U401") (pin "61") (pinfunction "XTAL2_61") (pintype "output"))
      (node (ref "Y401") (pin "3") (pinfunction "2_3") (pintype "passive"))
    )
    (net (code "63") (name "Net-(U501-BYP)") (class "Default")
      (node (ref "C504") (pin "1") (pinfunction "1_1") (pintype "passive"))
      (node (ref "U501") (pin "4") (pinfunction "BYP_4") (pintype "bidirectional"))
    )
    (net (code "64") (name "VCC") (class "Default")
      (node (ref "C205") (pin "1") (pinfunction "1_1") (pintype "passive"))
      (node (ref "C407") (pin "1") (pinfunction "1_1") (pintype "passive"))
      (node (ref "C423") (pin "1") (pinfunction "1_1") (pintype "passive"))
      (node (ref "C432") (pin "1") (pinfunction "1_1") (pintype "passive"))
      (node (ref "C443") (pin "1") (pinfunction "1_1") (pintype "passive"))
      (node (ref "C451") (pin "1") (pinfunction "1_1") (pintype "passive"))
      (node (ref "C463") (pin "1") (pinfunction "1_1") (pintype "passive"))
      (node (ref "C501") (pin "1") (pinfunction "1_1") (pintype "passive"))
      (node (ref "C701") (pin "1") (pinfunction "1_1") (pintype "passive"))
      (node (ref "J401") (pin "6") (pinfunction "6_6") (pintype "passive"))
      (node (ref "J404") (pin "3") (pinfunction "3_3") (pintype "passive"))
      (node (ref "J406") (pin "11") (pinfunction "11_11") (pintype "passive"))
      (node (ref "Q050") (pin "2") (pinfunction "S_2") (pintype "passive"))
      (node (ref "R015") (pin "1") (pinfunction "1_1") (pintype "passive"))
      (node (ref "R401") (pin "1") (pinfunction "1_1") (pintype "passive"))
      (node (ref "R401") (pin "2") (pinfunction "1_2") (pintype "passive"))
      (node (ref "R401") (pin "3") (pinfunction "1_3") (pintype "passive"))
      (node (ref "R401") (pin "4") (pinfunction "1_4") (pintype "passive"))
      (node (ref "S401") (pin "2") (pinfunction "2_2") (pintype "passive"))
      (node (ref "U201") (pin "5") (pinfunction "VOUT_5") (pintype "bidirectional"))
      (node (ref "U202") (pin "3") (pinfunction "VCC_3") (pintype "bidirectional"))
      (node (ref "U401") (pin "23") (pinfunction "VDD3-1_23") (pintype "power_in"))
      (node (ref "U401") (pin "43") (pinfunction "VDD3-2_43") (pintype "power_in"))
      (node (ref "U401") (pin "49") (pinfunction "VBAT_49") (pintype "power_in"))
      (node (ref "U401") (pin "51") (pinfunction "VDD3-3_51") (pintype "power_in"))
      (node (ref "U401") (pin "63") (pinfunction "VREF_63") (pintype "input"))
      (node (ref "U401") (pin "7") (pinfunction "VDDA3_7") (pintype "power_in"))
      (node (ref "U402") (pin "1") (pinfunction "VCC_1") (pintype "bidirectional"))
      (node (ref "U501") (pin "1") (pinfunction "VIN_1") (pintype "bidirectional"))
      (node (ref "U501") (pin "3") (pinfunction "EN_3") (pintype "bidirectional"))
      (node (ref "U502") (pin "11") (pinfunction "VCC_HI_11") (pintype "power_in"))
      (node (ref "U701") (pin "4") (pinfunction "VCC_4") (pintype "bidirectional"))
    )
    (net (code "65") (name "unconnected-(U401-P1.16(TRACEPKT0)-Pad16)") (class "Default")
      (node (ref "U401") (pin "16") (pinfunction "P1.16(TRACEPKT0)_16") (pintype "bidirectional"))
    )
    (net (code "66") (name "unconnected-(U401-P1.17(TRACEPKT1)-Pad12)") (class "Default")
      (node (ref "U401") (pin "12") (pinfunction "P1.17(TRACEPKT1)_12") (pintype "bidirectional"))
    )
    (net (code "67") (name "unconnected-(U401-P1.18(TRACEPKT2)-Pad8)") (class "Default")
      (node (ref "U401") (pin "8") (pinfunction "P1.18(TRACEPKT2)_8") (pintype "bidirectional"))
    )
    (net (code "68") (name "unconnected-(U401-P1.19(TRACEPKT3)-Pad4)") (class "Default")
      (node (ref "U401") (pin "4") (pinfunction "P1.19(TRACEPKT3)_4") (pintype "bidirectional"))
    )
    (net (code "69") (name "unconnected-(U401-P1.20(TRACESYNC)-Pad48)") (class "Default")
      (node (ref "U401") (pin "48") (pinfunction "P1.20(TRACESYNC)_48") (pintype "bidirectional"))
    )
    (net (code "70") (name "unconnected-(U401-P1.21(PIPESTAT0)-Pad44)") (class "Default")
      (node (ref "U401") (pin "44") (pinfunction "P1.21(PIPESTAT0)_44") (pintype "bidirectional"))
    )
    (net (code "71") (name "unconnected-(U401-P1.22(PIPESTAT1)-Pad40)") (class "Default")
      (node (ref "U401") (pin "40") (pinfunction "P1.22(PIPESTAT1)_40") (pintype "bidirectional"))
    )
    (net (code "72") (name "unconnected-(U401-P1.23(PIPESTAT2)-Pad36)") (class "Default")
      (node (ref "U401") (pin "36") (pinfunction "P1.23(PIPESTAT2)_36") (pintype "bidirectional"))
    )
    (net (code "73") (name "unconnected-(U401-P1.25(EXTIN0)-Pad28)") (class "Default")
      (node (ref "U401") (pin "28") (pinfunction "P1.25(EXTIN0)_28") (pintype "bidirectional"))
    )
    (net (code "74") (name "unconnected-(U401-P1.26(RTCK)-Pad24)") (class "Default")
      (node (ref "U401") (pin "24") (pinfunction "P1.26(RTCK)_24") (pintype "bidirectional"))
    )
    (net (code "75") (name "unconnected-(U401-P1.27(TDO)-Pad64)") (class "Default")
      (node (ref "U401") (pin "64") (pinfunction "P1.27(TDO)_64") (pintype "bidirectional"))
    )
    (net (code "76") (name "unconnected-(U401-P1.28(TDI)-Pad60)") (class "Default")
      (node (ref "U401") (pin "60") (pinfunction "P1.28(TDI)_60") (pintype "bidirectional"))
    )
    (net (code "77") (name "unconnected-(U401-P1.29(TCK)-Pad56)") (class "Default")
      (node (ref "U401") (pin "56") (pinfunction "P1.29(TCK)_56") (pintype "bidirectional"))
    )
    (net (code "78") (name "unconnected-(U401-P1.30(TMS)-Pad52)") (class "Default")
      (node (ref "U401") (pin "52") (pinfunction "P1.30(TMS)_52") (pintype "bidirectional"))
    )
    (net (code "79") (name "unconnected-(U401-P1.31({slash}TRST)-Pad20)") (class "Default")
      (node (ref "U401") (pin "20") (pinfunction "P1.31(/TRST)_20") (pintype "bidirectional"))
    )
    (net (code "80") (name "unconnected-(U701-CD-PadCD1)") (class "Default")
      (node (ref "U701") (pin "CD1") (pinfunction "CD_CD1") (pintype "bidirectional"))
    )
    (net (code "81") (name "unconnected-(U701-NC-Pad1)") (class "Default")
      (node (ref "U701") (pin "1") (pinfunction "NC_1") (pintype "bidirectional"))
    )
    (net (code "82") (name "unconnected-(U701-RSV-Pad8)") (class "Default")
      (node (ref "U701") (pin "8") (pinfunction "RSV_8") (pintype "bidirectional"))
    )
  )
)
